# relay.net
KiCad netlist of a schematic drawn in EAGLE
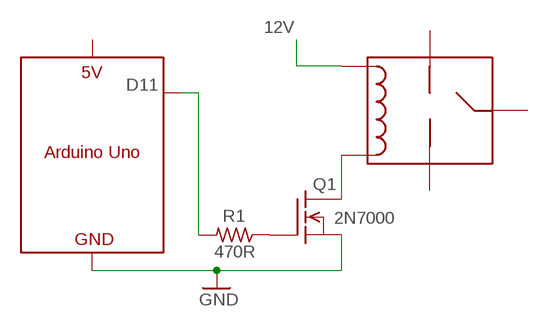
[diagram p0: schematic, sheet 1]

(export (version "E")
  (design (tool "Eeschema 10.0.6"))
  (components
    (comp (ref "K2")
      (value "RELAY-HLS8L-DC3V-S-C(5P-19X15MM)")
      (footprint "eagle-import:REY5-19.0X15.0X15.0MM")
      (fields (field (name "MPN") "HLS8L-DC3V-S-C"))
      (libsource (lib "eagle-import") (part "RELAY-HLS8L-DC3V-S-C(5P-19X15MM)"))
    )
    (comp (ref "Q1")
      (value "2N7000")
      (footprint "eagle-import:TO92")
      (libsource (lib "eagle-import") (part "BSS101"))
    )
    (comp (ref "R1")
      (value "470R")
      (footprint "eagle-import:M1206")
      (libsource (lib "eagle-import") (part "R-US_M1206"))
    )
    (comp (ref "U$1")
      (value "ARDUINO_1_PIN")
      (footprint "eagle-import:ARDUINO_1_PIN")
      (libsource (lib "eagle-import") (part "ARDUINO_1_PIN"))
    )
  )
  (nets
    (net (code "1") (name "GND") (class "Default")
      (node (ref "Q1") (pin "3") (pinfunction "S_3") (pintype "passive"))
      (node (ref "U$1") (pin "GND") (pinfunction "GND_GND") (pintype "bidirectional"))
    )
    (net (code "2") (name "Net-(K2-V-)") (class "Default")
      (node (ref "K2") (pin "3") (pinfunction "V-_3") (pintype "bidirectional"))
      (node (ref "Q1") (pin "1") (pinfunction "D_1") (pintype "passive"))
    )
    (net (code "3") (name "Net-(Q1-G)") (class "Default")
      (node (ref "Q1") (pin "2") (pinfunction "G_2") (pintype "passive"))
      (node (ref "R1") (pin "1") (pinfunction "1_1") (pintype "passive"))
    )
    (net (code "4") (name "Net-(R1-Pad2)") (class "Default")
      (node (ref "R1") (pin "2") (pinfunction "2_2") (pintype "passive"))
      (node (ref "U$1") (pin "PIN1") (pinfunction "PIN1_PIN1") (pintype "bidirectional"))
    )
    (net (code "5") (name "unconnected-(K2-COM-Pad1)") (class "Default")
      (node (ref "K2") (pin "1") (pinfunction "COM_1") (pintype "bidirectional"))
    )
    (net (code "6") (name "unconnected-(K2-NC-Pad5)") (class "Default")
      (node (ref "K2") (pin "5") (pinfunction "NC_5") (pintype "bidirectional"))
    )
    (net (code "7") (name "unconnected-(K2-NO-Pad4)") (class "Default")
      (node (ref "K2") (pin "4") (pinfunction "NO_4") (pintype "bidirectional"))
    )
    (net (code "8") (name "unconnected-(K2-V+-Pad2)") (class "Default")
      (node (ref "K2") (pin "2") (pinfunction "V+_2") (pintype "bidirectional"))
    )
    (net (code "9") (name "unconnected-(U$1-Pad5V)") (class "Default")
      (node (ref "U$1") (pin "5V") (pinfunction "5V_5V") (pintype "bidirectional"))
    )
  )
)
